# Schemat.net
KiCad netlist of a schematic drawn in EAGLE
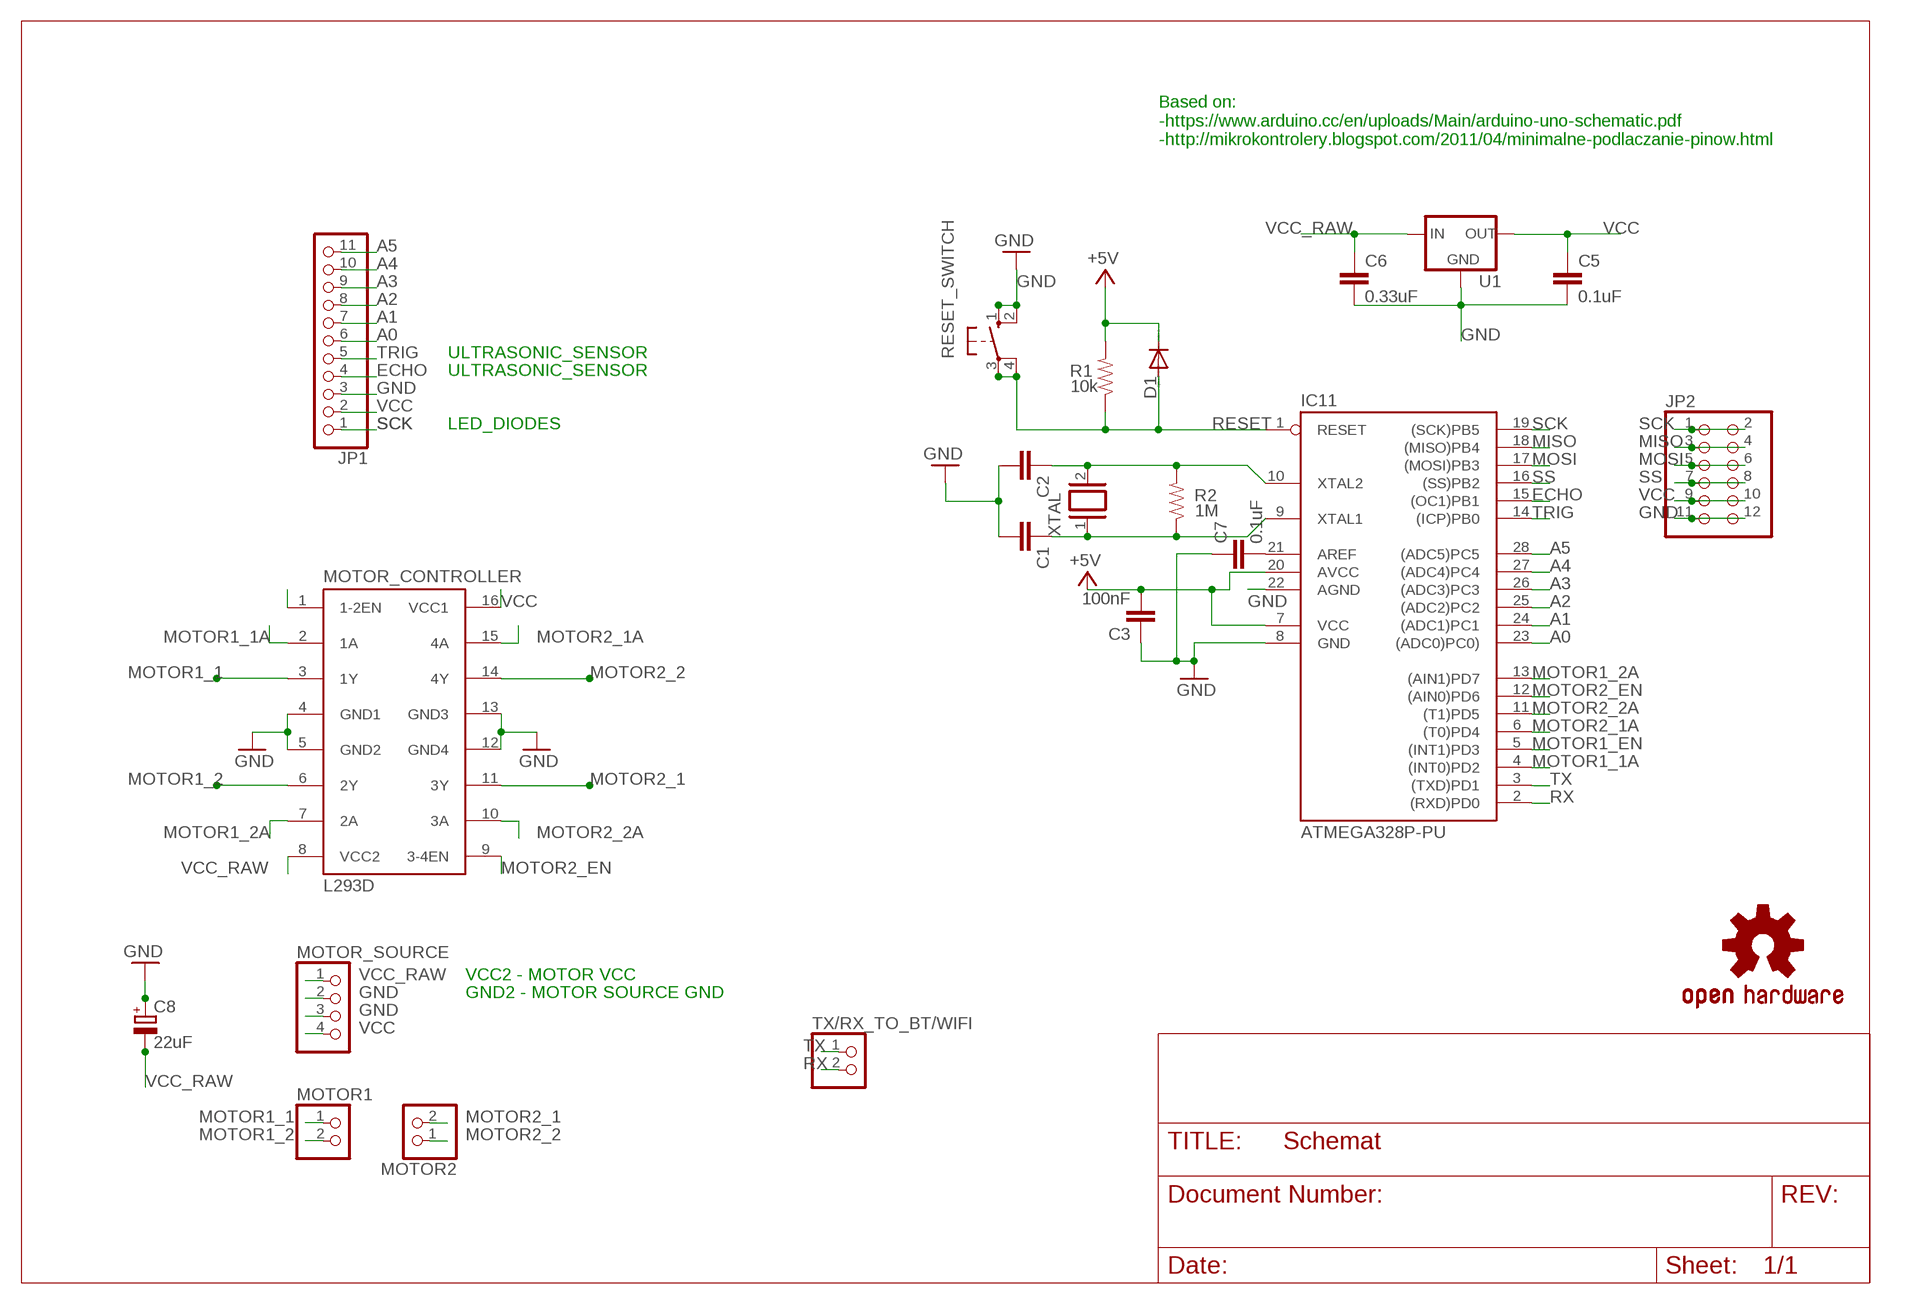
[diagram p0: schematic, sheet 1]

(export (version "E")
  (design (tool "Eeschema 10.0.6"))
  (components
    (comp (ref "C1")
      (value "C-EU025-030X050")
      (footprint "eagle-import:C025-030X050")
      (libsource (lib "eagle-import") (part "C-EU025-030X050"))
    )
    (comp (ref "C2")
      (value "C-EU025-030X050")
      (footprint "eagle-import:C025-030X050")
      (libsource (lib "eagle-import") (part "C-EU025-030X050"))
    )
    (comp (ref "C3")
      (value "100nF")
      (footprint "eagle-import:C025-030X050")
      (libsource (lib "eagle-import") (part "C-EU025-030X050"))
    )
    (comp (ref "C5")
      (value "0.1uF")
      (footprint "eagle-import:CAP-PTH-SMALL-KIT")
      (libsource (lib "eagle-import") (part "0.1UF-KIT-EZ-50V-20%"))
    )
    (comp (ref "C6")
      (value "0.33uF")
      (footprint "eagle-import:CAP-PTH-SMALL-KIT")
      (libsource (lib "eagle-import") (part "0.1UF-KIT-EZ-50V-20%"))
    )
    (comp (ref "C7")
      (value "0.1uF")
      (footprint "eagle-import:C025-030X050")
      (libsource (lib "eagle-import") (part "C-EU025-030X050"))
    )
    (comp (ref "C8")
      (value "22uF")
      (footprint "eagle-import:E2,5-6E")
      (libsource (lib "eagle-import") (part "CPOL-EUE2,5-6E"))
    )
    (comp (ref "D1")
      (value "1N4004")
      (footprint "eagle-import:DO41-10")
      (libsource (lib "eagle-import") (part "1N4004"))
    )
    (comp (ref "IC11")
      (value "ATMEGA328P-PU")
      (footprint "eagle-import:DIL28-3")
      (libsource (lib "eagle-import") (part "ATMEGA328P-PU"))
    )
    (comp (ref "JP1")
      (value "PINHD-1X11")
      (footprint "eagle-import:1X11")
      (libsource (lib "eagle-import") (part "PINHD-1X11"))
    )
    (comp (ref "JP2")
      (value "PINHD-2X6")
      (footprint "eagle-import:2X06")
      (libsource (lib "eagle-import") (part "PINHD-2X6"))
    )
    (comp (ref "LOGO1")
      (value "OSHW-LOGOS-COPPER")
      (footprint "eagle-import:OSHW-LOGO-S_COPPER")
      (libsource (lib "eagle-import") (part "OSHW-LOGOS-COPPER"))
    )
    (comp (ref "MOTOR1")
      (value "PINHD-1X2/90")
      (footprint "eagle-import:1X02_90")
      (libsource (lib "eagle-import") (part "PINHD-1X2/90"))
    )
    (comp (ref "MOTOR2")
      (value "PINHD-1X2/90")
      (footprint "eagle-import:1X02_90")
      (libsource (lib "eagle-import") (part "PINHD-1X2/90"))
    )
    (comp (ref "MOTOR_CONTROLLER")
      (value "L293D")
      (footprint "eagle-import:DIL16")
      (libsource (lib "eagle-import") (part "L293D"))
    )
    (comp (ref "MOTOR_SOURCE")
      (value "PINHD-1X4")
      (footprint "eagle-import:1X04")
      (libsource (lib "eagle-import") (part "PINHD-1X4"))
    )
    (comp (ref "R1")
      (value "10k")
      (footprint "eagle-import:AXIAL-0.3")
      (libsource (lib "eagle-import") (part "RESISTORAXIAL-0.3"))
    )
    (comp (ref "R2")
      (value "1M")
      (footprint "eagle-import:AXIAL-0.3")
      (libsource (lib "eagle-import") (part "RESISTORAXIAL-0.3"))
    )
    (comp (ref "RESET_SWITCH")
      (value "10-XX")
      (footprint "eagle-import:B3F-10XX")
      (fields (field (name "MPN") "B3F-1000"))
      (libsource (lib "eagle-import") (part "10-XX"))
    )
    (comp (ref "TX/RX_TO_BT/WIFI")
      (value "PINHD-1X2/90")
      (footprint "eagle-import:1X02_90")
      (libsource (lib "eagle-import") (part "PINHD-1X2/90"))
    )
    (comp (ref "U1")
      (value "V_REG_78XX-TO-220")
      (footprint "eagle-import:TO-220-ALT")
      (libsource (lib "eagle-import") (part "V_REG_78XX-TO-220"))
    )
    (comp (ref "XTAL")
      (value "XTAL/S")
      (footprint "eagle-import:QS")
      (libsource (lib "eagle-import") (part "XTAL/S"))
    )
  )
  (nets
    (net (code "1") (name "+5V") (class "Default")
      (node (ref "C3") (pin "2") (pinfunction "2_2") (pintype "passive"))
      (node (ref "C5") (pin "1") (pinfunction "1_1") (pintype "passive"))
      (node (ref "D1") (pin "C") (pinfunction "C_C") (pintype "passive"))
      (node (ref "IC11") (pin "20") (pinfunction "AVCC_20") (pintype "power_in"))
      (node (ref "IC11") (pin "7") (pinfunction "VCC_7") (pintype "power_in"))
      (node (ref "JP1") (pin "2") (pinfunction "2_2") (pintype "passive"))
      (node (ref "JP2") (pin "10") (pinfunction "10_10") (pintype "passive"))
      (node (ref "JP2") (pin "9") (pinfunction "9_9") (pintype "passive"))
      (node (ref "MOTOR_CONTROLLER") (pin "16") (pinfunction "VCC1_16") (pintype "power_in"))
      (node (ref "MOTOR_SOURCE") (pin "4") (pinfunction "4_4") (pintype "passive"))
      (node (ref "R1") (pin "P$2") (pinfunction "2_P$2") (pintype "passive"))
      (node (ref "U1") (pin "OUT") (pinfunction "OUT_OUT") (pintype "passive"))
    )
    (net (code "2") (name "/A0") (class "Default")
      (node (ref "IC11") (pin "23") (pinfunction "(ADC0)PC0)_23") (pintype "bidirectional"))
      (node (ref "JP1") (pin "6") (pinfunction "6_6") (pintype "passive"))
    )
    (net (code "3") (name "/A1") (class "Default")
      (node (ref "IC11") (pin "24") (pinfunction "(ADC1)PC1_24") (pintype "bidirectional"))
      (node (ref "JP1") (pin "7") (pinfunction "7_7") (pintype "passive"))
    )
    (net (code "4") (name "/A2") (class "Default")
      (node (ref "IC11") (pin "25") (pinfunction "(ADC2)PC2_25") (pintype "bidirectional"))
      (node (ref "JP1") (pin "8") (pinfunction "8_8") (pintype "passive"))
    )
    (net (code "5") (name "/A3") (class "Default")
      (node (ref "IC11") (pin "26") (pinfunction "(ADC3)PC3_26") (pintype "bidirectional"))
      (node (ref "JP1") (pin "9") (pinfunction "9_9") (pintype "passive"))
    )
    (net (code "6") (name "/A4") (class "Default")
      (node (ref "IC11") (pin "27") (pinfunction "(ADC4)PC4_27") (pintype "bidirectional"))
      (node (ref "JP1") (pin "10") (pinfunction "10_10") (pintype "passive"))
    )
    (net (code "7") (name "/A5") (class "Default")
      (node (ref "IC11") (pin "28") (pinfunction "(ADC5)PC5_28") (pintype "bidirectional"))
      (node (ref "JP1") (pin "11") (pinfunction "11_11") (pintype "passive"))
    )
    (net (code "8") (name "/ECHO") (class "Default")
      (node (ref "IC11") (pin "15") (pinfunction "(OC1)PB1_15") (pintype "bidirectional"))
      (node (ref "JP1") (pin "4") (pinfunction "4_4") (pintype "passive"))
    )
    (net (code "9") (name "/MISO") (class "Default")
      (node (ref "IC11") (pin "18") (pinfunction "(MISO)PB4_18") (pintype "bidirectional"))
      (node (ref "JP2") (pin "3") (pinfunction "3_3") (pintype "passive"))
      (node (ref "JP2") (pin "4") (pinfunction "4_4") (pintype "passive"))
    )
    (net (code "10") (name "/MOSI") (class "Default")
      (node (ref "IC11") (pin "17") (pinfunction "(MOSI)PB3_17") (pintype "bidirectional"))
      (node (ref "JP2") (pin "5") (pinfunction "5_5") (pintype "passive"))
      (node (ref "JP2") (pin "6") (pinfunction "6_6") (pintype "passive"))
    )
    (net (code "11") (name "/MOTOR1_1") (class "Default")
      (node (ref "MOTOR1") (pin "1") (pinfunction "1_1") (pintype "passive"))
      (node (ref "MOTOR_CONTROLLER") (pin "3") (pinfunction "1Y_3") (pintype "output"))
    )
    (net (code "12") (name "/MOTOR1_1A") (class "Default")
      (node (ref "IC11") (pin "4") (pinfunction "(INT0)PD2_4") (pintype "bidirectional"))
      (node (ref "MOTOR_CONTROLLER") (pin "2") (pinfunction "1A_2") (pintype "input"))
    )
    (net (code "13") (name "/MOTOR1_2") (class "Default")
      (node (ref "MOTOR1") (pin "2") (pinfunction "2_2") (pintype "passive"))
      (node (ref "MOTOR_CONTROLLER") (pin "6") (pinfunction "2Y_6") (pintype "output"))
    )
    (net (code "14") (name "/MOTOR1_2A") (class "Default")
      (node (ref "IC11") (pin "13") (pinfunction "(AIN1)PD7_13") (pintype "bidirectional"))
      (node (ref "MOTOR_CONTROLLER") (pin "7") (pinfunction "2A_7") (pintype "input"))
    )
    (net (code "15") (name "/MOTOR1_EN") (class "Default")
      (node (ref "IC11") (pin "5") (pinfunction "(INT1)PD3_5") (pintype "bidirectional"))
      (node (ref "MOTOR_CONTROLLER") (pin "1") (pinfunction "1-2EN_1") (pintype "input"))
    )
    (net (code "16") (name "/MOTOR2_1") (class "Default")
      (node (ref "MOTOR2") (pin "2") (pinfunction "2_2") (pintype "passive"))
      (node (ref "MOTOR_CONTROLLER") (pin "11") (pinfunction "3Y_11") (pintype "output"))
    )
    (net (code "17") (name "/MOTOR2_1A") (class "Default")
      (node (ref "IC11") (pin "6") (pinfunction "(T0)PD4_6") (pintype "bidirectional"))
      (node (ref "MOTOR_CONTROLLER") (pin "15") (pinfunction "4A_15") (pintype "input"))
    )
    (net (code "18") (name "/MOTOR2_2") (class "Default")
      (node (ref "MOTOR2") (pin "1") (pinfunction "1_1") (pintype "passive"))
      (node (ref "MOTOR_CONTROLLER") (pin "14") (pinfunction "4Y_14") (pintype "output"))
    )
    (net (code "19") (name "/MOTOR2_2A") (class "Default")
      (node (ref "IC11") (pin "11") (pinfunction "(T1)PD5_11") (pintype "bidirectional"))
      (node (ref "MOTOR_CONTROLLER") (pin "10") (pinfunction "3A_10") (pintype "input"))
    )
    (net (code "20") (name "/MOTOR2_EN") (class "Default")
      (node (ref "IC11") (pin "12") (pinfunction "(AIN0)PD6_12") (pintype "bidirectional"))
      (node (ref "MOTOR_CONTROLLER") (pin "9") (pinfunction "3-4EN_9") (pintype "input"))
    )
    (net (code "21") (name "/RESET") (class "Default")
      (node (ref "D1") (pin "A") (pinfunction "A_A") (pintype "passive"))
      (node (ref "IC11") (pin "1") (pinfunction "RESET_1") (pintype "input"))
      (node (ref "R1") (pin "P$1") (pinfunction "1_P$1") (pintype "passive"))
      (node (ref "RESET_SWITCH") (pin "3") (pinfunction "P_3") (pintype "passive"))
      (node (ref "RESET_SWITCH") (pin "4") (pinfunction "P1_4") (pintype "passive"))
    )
    (net (code "22") (name "/RX") (class "Default")
      (node (ref "IC11") (pin "2") (pinfunction "(RXD)PD0_2") (pintype "bidirectional"))
      (node (ref "TX/RX_TO_BT/WIFI") (pin "2") (pinfunction "2_2") (pintype "passive"))
    )
    (net (code "23") (name "/SCK") (class "Default")
      (node (ref "IC11") (pin "19") (pinfunction "(SCK)PB5_19") (pintype "bidirectional"))
      (node (ref "JP1") (pin "1") (pinfunction "1_1") (pintype "passive"))
      (node (ref "JP2") (pin "1") (pinfunction "1_1") (pintype "passive"))
      (node (ref "JP2") (pin "2") (pinfunction "2_2") (pintype "passive"))
    )
    (net (code "24") (name "/SS") (class "Default")
      (node (ref "IC11") (pin "16") (pinfunction "(SS)PB2_16") (pintype "bidirectional"))
      (node (ref "JP2") (pin "7") (pinfunction "7_7") (pintype "passive"))
      (node (ref "JP2") (pin "8") (pinfunction "8_8") (pintype "passive"))
    )
    (net (code "25") (name "/TRIG") (class "Default")
      (node (ref "IC11") (pin "14") (pinfunction "(ICP)PB0_14") (pintype "bidirectional"))
      (node (ref "JP1") (pin "5") (pinfunction "5_5") (pintype "passive"))
    )
    (net (code "26") (name "/TX") (class "Default")
      (node (ref "IC11") (pin "3") (pinfunction "(TXD)PD1_3") (pintype "bidirectional"))
      (node (ref "TX/RX_TO_BT/WIFI") (pin "1") (pinfunction "1_1") (pintype "passive"))
    )
    (net (code "27") (name "/VCC_RAW") (class "Default")
      (node (ref "C6") (pin "1") (pinfunction "1_1") (pintype "passive"))
      (node (ref "C8") (pin "-") (pinfunction "-_-") (pintype "passive"))
      (node (ref "MOTOR_CONTROLLER") (pin "8") (pinfunction "VCC2_8") (pintype "power_in"))
      (node (ref "MOTOR_SOURCE") (pin "1") (pinfunction "1_1") (pintype "passive"))
      (node (ref "U1") (pin "IN") (pinfunction "IN_IN") (pintype "input"))
    )
    (net (code "28") (name "GND") (class "Default")
      (node (ref "C1") (pin "2") (pinfunction "2_2") (pintype "passive"))
      (node (ref "C2") (pin "2") (pinfunction "2_2") (pintype "passive"))
      (node (ref "C3") (pin "1") (pinfunction "1_1") (pintype "passive"))
      (node (ref "C5") (pin "2") (pinfunction "2_2") (pintype "passive"))
      (node (ref "C6") (pin "2") (pinfunction "2_2") (pintype "passive"))
      (node (ref "C7") (pin "1") (pinfunction "1_1") (pintype "passive"))
      (node (ref "C8") (pin "+") (pinfunction "+_+") (pintype "passive"))
      (node (ref "IC11") (pin "22") (pinfunction "AGND_22") (pintype "power_in"))
      (node (ref "IC11") (pin "8") (pinfunction "GND_8") (pintype "power_in"))
      (node (ref "JP1") (pin "3") (pinfunction "3_3") (pintype "passive"))
      (node (ref "JP2") (pin "11") (pinfunction "11_11") (pintype "passive"))
      (node (ref "JP2") (pin "12") (pinfunction "12_12") (pintype "passive"))
      (node (ref "MOTOR_CONTROLLER") (pin "12") (pinfunction "GND4_12") (pintype "power_in"))
      (node (ref "MOTOR_CONTROLLER") (pin "13") (pinfunction "GND3_13") (pintype "power_in"))
      (node (ref "MOTOR_CONTROLLER") (pin "4") (pinfunction "GND1_4") (pintype "power_in"))
      (node (ref "MOTOR_CONTROLLER") (pin "5") (pinfunction "GND2_5") (pintype "power_in"))
      (node (ref "MOTOR_SOURCE") (pin "2") (pinfunction "2_2") (pintype "passive"))
      (node (ref "MOTOR_SOURCE") (pin "3") (pinfunction "3_3") (pintype "passive"))
      (node (ref "RESET_SWITCH") (pin "1") (pinfunction "S_1") (pintype "passive"))
      (node (ref "RESET_SWITCH") (pin "2") (pinfunction "S1_2") (pintype "passive"))
      (node (ref "U1") (pin "GND") (pinfunction "GND_GND") (pintype "input"))
    )
    (net (code "29") (name "Net-(IC11-AREF)") (class "Default")
      (node (ref "C7") (pin "2") (pinfunction "2_2") (pintype "passive"))
      (node (ref "IC11") (pin "21") (pinfunction "AREF_21") (pintype "passive"))
    )
    (net (code "30") (name "Net-(IC11-XTAL1)") (class "Default")
      (node (ref "C1") (pin "1") (pinfunction "1_1") (pintype "passive"))
      (node (ref "IC11") (pin "9") (pinfunction "XTAL1_9") (pintype "bidirectional"))
      (node (ref "R2") (pin "P$1") (pinfunction "1_P$1") (pintype "passive"))
      (node (ref "XTAL") (pin "1") (pinfunction "1_1") (pintype "passive"))
    )
    (net (code "31") (name "Net-(IC11-XTAL2)") (class "Default")
      (node (ref "C2") (pin "1") (pinfunction "1_1") (pintype "passive"))
      (node (ref "IC11") (pin "10") (pinfunction "XTAL2_10") (pintype "bidirectional"))
      (node (ref "R2") (pin "P$2") (pinfunction "2_P$2") (pintype "passive"))
      (node (ref "XTAL") (pin "2") (pinfunction "2_2") (pintype "passive"))
    )
  )
)
